# 11_-MAIN_POWER.net
KiCad netlist of a schematic drawn in Altium Designer
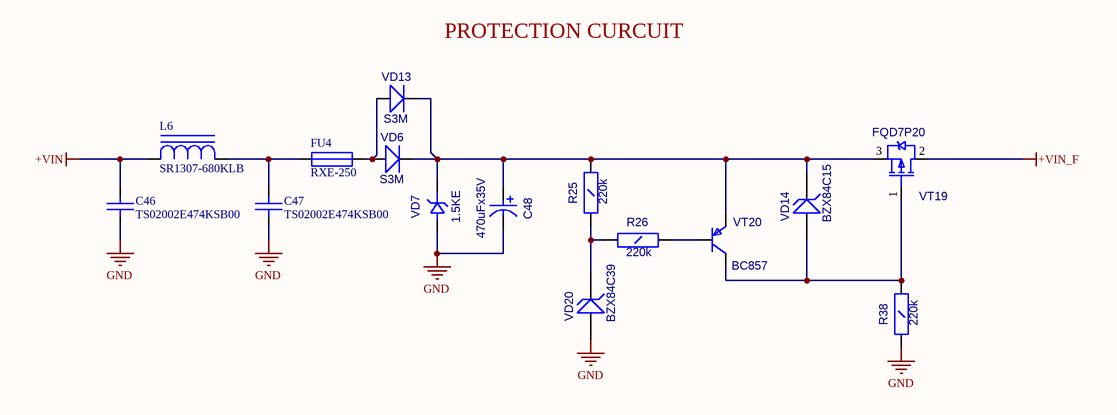
[diagram p0: [11]-MAIN_POWER.SchDoc]

(export (version "E")
  (design (tool "Eeschema 10.0.6"))
  (components
    (comp (ref "C46")
      (value "TS02002E474KSB00")
      (footprint "CAP_ML_18x7x13")
      (libsource (lib "fizik_lib (1)") (part "CAP_HV_18x7x13"))
    )
    (comp (ref "C47")
      (value "TS02002E474KSB00")
      (footprint "CAP_ML_18x7x13")
      (libsource (lib "fizik_lib (1)") (part "CAP_HV_18x7x13"))
    )
    (comp (ref "C48")
      (value "470uFx35V")
      (footprint "CAP10x16_FLAT")
      (description "Radial capacitor")
      (libsource (lib "fizik_lib (1)") (part "CAP_10mm"))
    )
    (comp (ref "FU4")
      (value "RXE-250")
      (footprint "RXE-250_FLAT")
      (libsource (lib "fizik_lib") (part "RXE-250"))
    )
    (comp (ref "L6")
      (value "SR1307-680KLB")
      (footprint "SR1307")
      (description "Power inductor")
      (libsource (lib "fizik_lib") (part "SR1307"))
    )
    (comp (ref "R25")
      (value "220k")
      (footprint "RC1206")
      (description "RC1206")
      (libsource (lib "fizik_lib") (part "RC1206"))
    )
    (comp (ref "R26")
      (value "220k")
      (footprint "RC1206")
      (description "RC1206")
      (libsource (lib "fizik_lib") (part "RC1206"))
    )
    (comp (ref "R38")
      (value "220k")
      (footprint "RC1206")
      (description "RC1206")
      (libsource (lib "fizik_lib") (part "RC1206"))
    )
    (comp (ref "VD6")
      (value "S3M")
      (footprint "SMC")
      (description "Schottky Rectifier")
      (libsource (lib "fizik_lib") (part "S3A"))
    )
    (comp (ref "VD7") (value "1.5KE") (footprint "DO-201") (libsource (lib "fizik_lib") (part "1.5KE")))
    (comp (ref "VD13")
      (value "S3M")
      (footprint "SMC")
      (description "Schottky Rectifier")
      (libsource (lib "fizik_lib") (part "S3A"))
    )
    (comp (ref "VD14")
      (value "BZX84C15")
      (footprint "SOT-23(123)")
      (description "Zener Voltage Regulator Diode")
      (libsource (lib "fizik_lib") (part "BZX84"))
    )
    (comp (ref "VD20")
      (value "BZX84C39")
      (footprint "SOT-23(123)")
      (description "Zener Voltage Regulator Diode")
      (libsource (lib "fizik_lib") (part "BZX84"))
    )
    (comp (ref "VT19")
      (value "FQD7P20")
      (footprint "D-PAK(TO-252AA)")
      (description "HEXFET Power MOSFET")
      (libsource (lib "gprs_modem_2") (part "IRFR9220"))
    )
    (comp (ref "VT20")
      (value "BC857")
      (footprint "SOT-23(123)")
      (description "PNP 100ma transistor")
      (libsource (lib "gprs_modem_2") (part "BC857B"))
    )
  )
  (nets
    (net (code "1") (name "+VIN") (class "Default")
      (node (ref "C46") (pin "2") (pinfunction "B_2") (pintype "passive"))
      (node (ref "L6") (pin "1") (pinfunction "C_1") (pintype "passive"))
    )
    (net (code "2") (name "+VIN_F") (class "Default")
      (node (ref "VT19") (pin "2") (pinfunction "D_2") (pintype "passive"))
    )
    (net (code "3") (name "GND") (class "Default")
      (node (ref "C46") (pin "1") (pinfunction "A_1") (pintype "passive"))
      (node (ref "C47") (pin "1") (pinfunction "A_1") (pintype "passive"))
      (node (ref "C48") (pin "1") (pintype "passive"))
      (node (ref "R38") (pin "1") (pinfunction "A_1") (pintype "passive"))
      (node (ref "VD20") (pin "1") (pinfunction "A_1") (pintype "passive"))
      (node (ref "VD7") (pin "1") (pinfunction "A_1") (pintype "passive"))
    )
    (net (code "4") (name "Net-(C47-B)") (class "Default")
      (node (ref "C47") (pin "2") (pinfunction "B_2") (pintype "passive"))
      (node (ref "FU4") (pin "1") (pintype "passive"))
      (node (ref "L6") (pin "2") (pinfunction "A_2") (pintype "passive"))
    )
    (net (code "5") (name "Net-(R25-A)") (class "Default")
      (node (ref "R25") (pin "1") (pinfunction "A_1") (pintype "passive"))
      (node (ref "R26") (pin "1") (pinfunction "A_1") (pintype "passive"))
      (node (ref "VD20") (pin "3") (pinfunction "K_3") (pintype "passive"))
    )
    (net (code "6") (name "Net-(R25-B)") (class "Default")
      (node (ref "C48") (pin "2") (pintype "passive"))
      (node (ref "R25") (pin "2") (pinfunction "B_2") (pintype "passive"))
      (node (ref "VD13") (pin "2") (pinfunction "K_2") (pintype "passive"))
      (node (ref "VD14") (pin "3") (pinfunction "K_3") (pintype "passive"))
      (node (ref "VD6") (pin "2") (pinfunction "K_2") (pintype "passive"))
      (node (ref "VD7") (pin "2") (pinfunction "K_2") (pintype "passive"))
      (node (ref "VT19") (pin "3") (pinfunction "S_3") (pintype "passive"))
      (node (ref "VT20") (pin "2") (pinfunction "E_2") (pintype "passive"))
    )
    (net (code "7") (name "Net-(R26-B)") (class "Default")
      (node (ref "R26") (pin "2") (pinfunction "B_2") (pintype "passive"))
      (node (ref "VT20") (pin "1") (pinfunction "B_1") (pintype "passive"))
    )
    (net (code "8") (name "Net-(R38-B)") (class "Default")
      (node (ref "R38") (pin "2") (pinfunction "B_2") (pintype "passive"))
      (node (ref "VD14") (pin "1") (pinfunction "A_1") (pintype "passive"))
      (node (ref "VT19") (pin "1") (pinfunction "G_1") (pintype "passive"))
      (node (ref "VT20") (pin "3") (pinfunction "C_3") (pintype "passive"))
    )
    (net (code "9") (name "Net-(VD13-A)") (class "Default")
      (node (ref "FU4") (pin "2") (pintype "passive"))
      (node (ref "VD13") (pin "1") (pinfunction "A_1") (pintype "passive"))
      (node (ref "VD6") (pin "1") (pinfunction "A_1") (pintype "passive"))
    )
  )
)
